# untitled.net
KiCad netlist of a schematic drawn in EAGLE
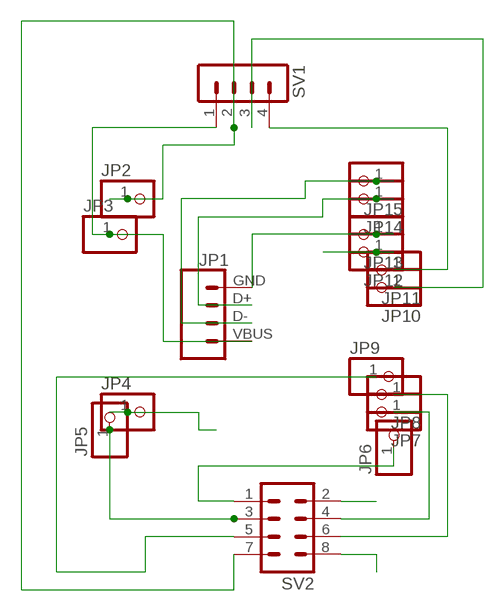
[diagram p0: schematic, sheet 1]

(export (version "E")
  (design (tool "Eeschema 10.0.6"))
  (components
    (comp (ref "JP1")
      (value "USB_SOLDER_PADS")
      (footprint "eagle-import:USB-SOLDER-PADS")
      (libsource (lib "eagle-import") (part "USB_SOLDER_PADS"))
    )
    (comp (ref "JP2")
      (value "PINHD-1X1")
      (footprint "eagle-import:1X01")
      (libsource (lib "eagle-import") (part "PINHD-1X1"))
    )
    (comp (ref "JP3")
      (value "PINHD-1X1")
      (footprint "eagle-import:1X01")
      (libsource (lib "eagle-import") (part "PINHD-1X1"))
    )
    (comp (ref "JP4")
      (value "PINHD-1X1")
      (footprint "eagle-import:1X01")
      (libsource (lib "eagle-import") (part "PINHD-1X1"))
    )
    (comp (ref "JP5")
      (value "PINHD-1X1")
      (footprint "eagle-import:1X01")
      (libsource (lib "eagle-import") (part "PINHD-1X1"))
    )
    (comp (ref "JP6")
      (value "PINHD-1X1")
      (footprint "eagle-import:1X01")
      (libsource (lib "eagle-import") (part "PINHD-1X1"))
    )
    (comp (ref "JP7")
      (value "PINHD-1X1")
      (footprint "eagle-import:1X01")
      (libsource (lib "eagle-import") (part "PINHD-1X1"))
    )
    (comp (ref "JP8")
      (value "PINHD-1X1")
      (footprint "eagle-import:1X01")
      (libsource (lib "eagle-import") (part "PINHD-1X1"))
    )
    (comp (ref "JP9")
      (value "PINHD-1X1")
      (footprint "eagle-import:1X01")
      (libsource (lib "eagle-import") (part "PINHD-1X1"))
    )
    (comp (ref "JP10")
      (value "PINHD-1X1")
      (footprint "eagle-import:1X01")
      (libsource (lib "eagle-import") (part "PINHD-1X1"))
    )
    (comp (ref "JP11")
      (value "PINHD-1X1")
      (footprint "eagle-import:1X01")
      (libsource (lib "eagle-import") (part "PINHD-1X1"))
    )
    (comp (ref "JP12")
      (value "PINHD-1X1")
      (footprint "eagle-import:1X01")
      (libsource (lib "eagle-import") (part "PINHD-1X1"))
    )
    (comp (ref "JP13")
      (value "PINHD-1X1")
      (footprint "eagle-import:1X01")
      (libsource (lib "eagle-import") (part "PINHD-1X1"))
    )
    (comp (ref "JP14")
      (value "PINHD-1X1")
      (footprint "eagle-import:1X01")
      (libsource (lib "eagle-import") (part "PINHD-1X1"))
    )
    (comp (ref "JP15")
      (value "PINHD-1X1")
      (footprint "eagle-import:1X01")
      (libsource (lib "eagle-import") (part "PINHD-1X1"))
    )
    (comp (ref "SV1")
      (value "MA04-1")
      (footprint "eagle-import:MA04-1")
      (libsource (lib "eagle-import") (part "MA04-1"))
    )
    (comp (ref "SV2")
      (value "MA04-2")
      (footprint "eagle-import:MA04-2")
      (libsource (lib "eagle-import") (part "MA04-2"))
    )
  )
  (nets
    (net (code "1") (name "Net-(JP1-1)") (class "Default")
      (node (ref "JP1") (pin "VBUS") (pinfunction "1_VBUS") (pintype "passive"))
      (node (ref "JP3") (pin "1") (pinfunction "1_1") (pintype "passive"))
      (node (ref "SV1") (pin "1") (pinfunction "1_1") (pintype "passive"))
    )
    (net (code "2") (name "Net-(JP1-2)") (class "Default")
      (node (ref "JP1") (pin "D-") (pinfunction "2_D-") (pintype "passive"))
      (node (ref "JP15") (pin "1") (pinfunction "1_1") (pintype "passive"))
    )
    (net (code "3") (name "Net-(JP1-3)") (class "Default")
      (node (ref "JP1") (pin "D+") (pinfunction "3_D+") (pintype "passive"))
      (node (ref "JP14") (pin "1") (pinfunction "1_1") (pintype "passive"))
    )
    (net (code "4") (name "Net-(JP1-4)") (class "Default")
      (node (ref "JP1") (pin "GND") (pinfunction "4_GND") (pintype "passive"))
      (node (ref "JP13") (pin "1") (pinfunction "1_1") (pintype "passive"))
    )
    (net (code "5") (name "Net-(JP2-Pad1)") (class "Default")
      (node (ref "JP2") (pin "1") (pinfunction "1_1") (pintype "passive"))
      (node (ref "SV1") (pin "2") (pinfunction "2_2") (pintype "passive"))
      (node (ref "SV2") (pin "7") (pinfunction "7_7") (pintype "passive"))
    )
    (net (code "6") (name "Net-(JP5-Pad1)") (class "Default")
      (node (ref "JP5") (pin "1") (pinfunction "1_1") (pintype "passive"))
      (node (ref "SV2") (pin "3") (pinfunction "3_3") (pintype "passive"))
    )
    (net (code "7") (name "Net-(JP6-Pad1)") (class "Default")
      (node (ref "JP6") (pin "1") (pinfunction "1_1") (pintype "passive"))
      (node (ref "SV2") (pin "1") (pinfunction "1_1") (pintype "passive"))
    )
    (net (code "8") (name "Net-(JP7-Pad1)") (class "Default")
      (node (ref "JP7") (pin "1") (pinfunction "1_1") (pintype "passive"))
      (node (ref "SV2") (pin "4") (pinfunction "4_4") (pintype "passive"))
    )
    (net (code "9") (name "Net-(JP8-Pad1)") (class "Default")
      (node (ref "JP8") (pin "1") (pinfunction "1_1") (pintype "passive"))
      (node (ref "SV2") (pin "6") (pinfunction "6_6") (pintype "passive"))
    )
    (net (code "10") (name "Net-(JP9-Pad1)") (class "Default")
      (node (ref "JP9") (pin "1") (pinfunction "1_1") (pintype "passive"))
      (node (ref "SV2") (pin "5") (pinfunction "5_5") (pintype "passive"))
    )
    (net (code "11") (name "Net-(JP10-Pad1)") (class "Default")
      (node (ref "JP10") (pin "1") (pinfunction "1_1") (pintype "passive"))
      (node (ref "SV1") (pin "3") (pinfunction "3_3") (pintype "passive"))
    )
    (net (code "12") (name "Net-(JP11-Pad1)") (class "Default")
      (node (ref "JP11") (pin "1") (pinfunction "1_1") (pintype "passive"))
      (node (ref "SV1") (pin "4") (pinfunction "4_4") (pintype "passive"))
    )
    (net (code "13") (name "unconnected-(JP4-Pad1)") (class "Default")
      (node (ref "JP4") (pin "1") (pinfunction "1_1") (pintype "passive"))
    )
    (net (code "14") (name "unconnected-(JP12-Pad1)") (class "Default")
      (node (ref "JP12") (pin "1") (pinfunction "1_1") (pintype "passive"))
    )
    (net (code "15") (name "unconnected-(SV2-Pad2)") (class "Default")
      (node (ref "SV2") (pin "2") (pinfunction "2_2") (pintype "passive"))
    )
    (net (code "16") (name "unconnected-(SV2-Pad8)") (class "Default")
      (node (ref "SV2") (pin "8") (pinfunction "8_8") (pintype "passive"))
    )
  )
)
